# 01_PSU.net
KiCad netlist of a schematic drawn in Altium Designer
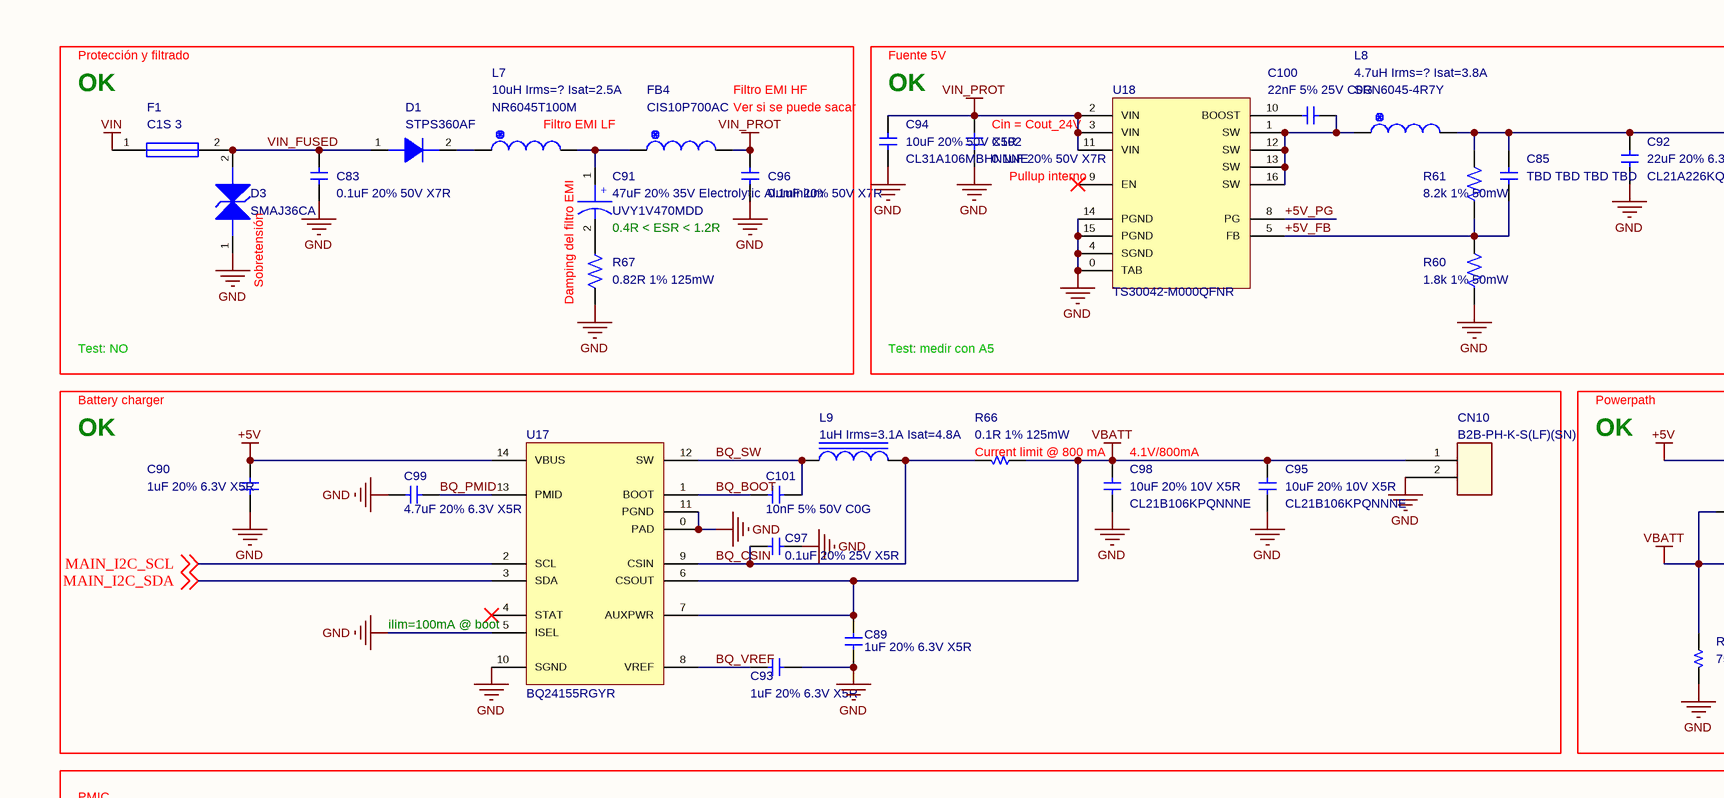
[diagram p0: 01_PSU.SchDoc, top left]
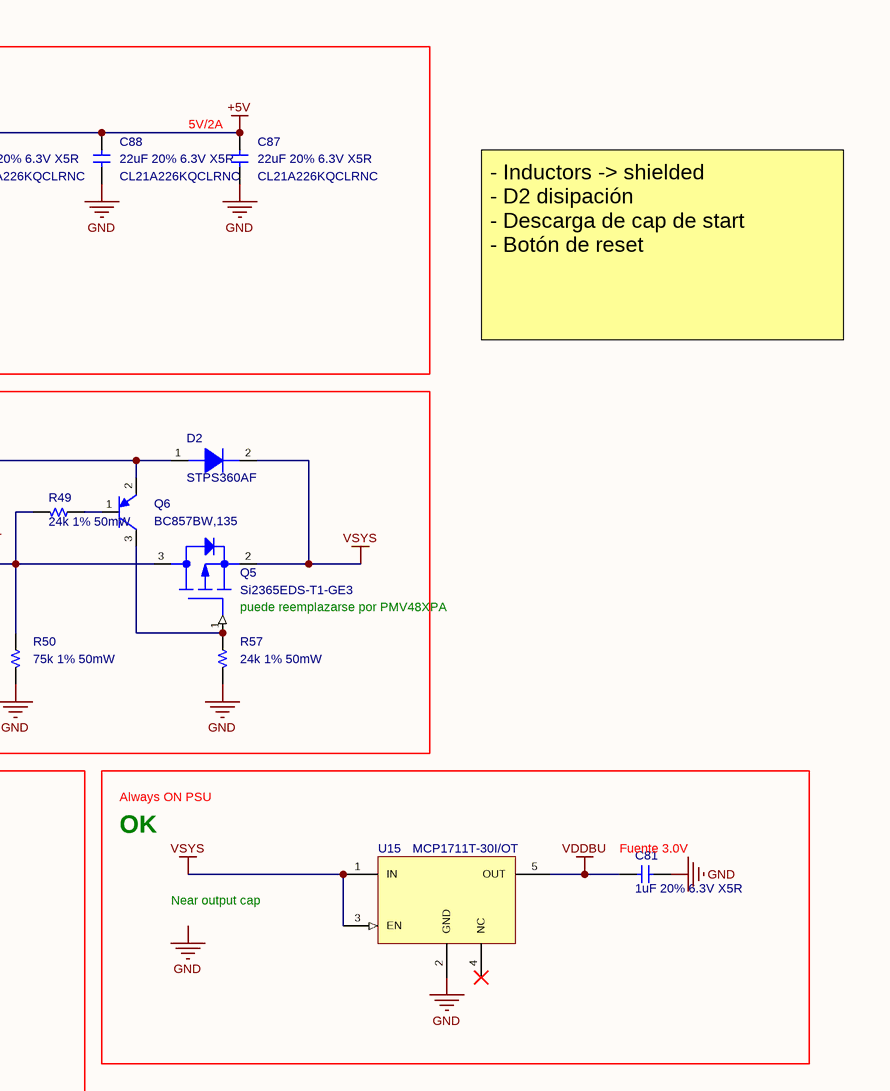
[diagram p1: 01_PSU.SchDoc, top right]
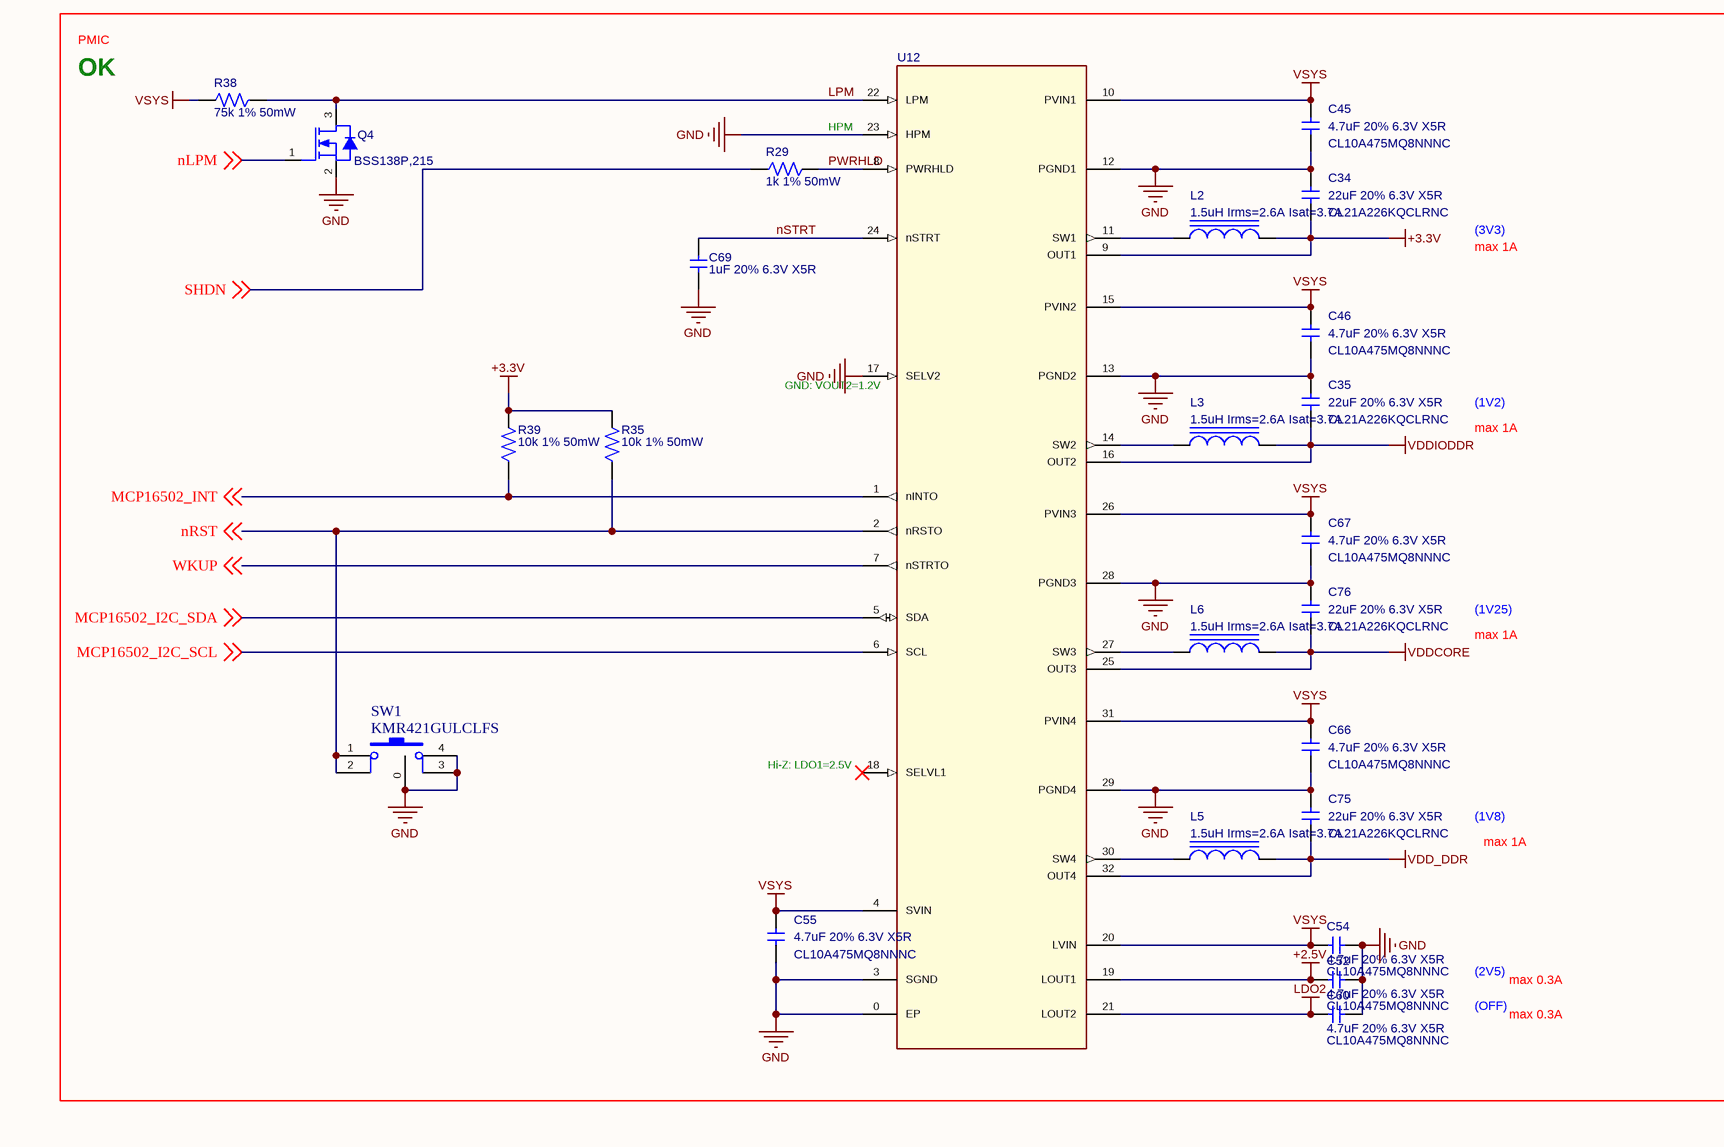
[diagram p2: 01_PSU.SchDoc, bottom left]

(export (version "E")
  (design (tool "Eeschema 10.0.6"))
  (components
    (comp (ref "C34")
      (value "22uF 20% 6.3V X5R")
      (footprint "CAPC2012X140N")
      (description "Capacitor, Ceramic")
      (fields
        (field (name "MFG") "SAMSUNG")
        (field (name "MFG_PN") "CL21A226KQCLRNC")
        (field (name "TOLERANCE") "20%")
        (field (name "FOOTPRINT CHECKED") "Assign OK, Footprint OK")
      )
      (libsource (lib "*") (part "C_Dup1"))
    )
    (comp (ref "C35")
      (value "22uF 20% 6.3V X5R")
      (footprint "CAPC2012X140N")
      (description "Capacitor, Ceramic")
      (fields
        (field (name "MFG") "SAMSUNG")
        (field (name "MFG_PN") "CL21A226KQCLRNC")
        (field (name "TOLERANCE") "20%")
        (field (name "FOOTPRINT CHECKED") "Assign OK, Footprint OK")
      )
      (libsource (lib "*") (part "C_Dup1"))
    )
    (comp (ref "C45")
      (value "4.7uF 20% 6.3V X5R")
      (footprint "CAPC1608X90N")
      (description "Capacitor, Ceramic")
      (fields
        (field (name "MFG") "SAMSUNG")
        (field (name "MFG_PN") "CL10A475MQ8NNNC")
        (field (name "TOLERANCE") "20%")
        (field (name "FOOTPRINT CHECKED") "Assign OK, Footprint OK")
      )
      (libsource (lib "*") (part "C_Dup1"))
    )
    (comp (ref "C46")
      (value "4.7uF 20% 6.3V X5R")
      (footprint "CAPC1608X90N")
      (description "Capacitor, Ceramic")
      (fields
        (field (name "MFG") "SAMSUNG")
        (field (name "MFG_PN") "CL10A475MQ8NNNC")
        (field (name "TOLERANCE") "20%")
        (field (name "FOOTPRINT CHECKED") "Assign OK, Footprint OK")
      )
      (libsource (lib "*") (part "C_Dup1"))
    )
    (comp (ref "C52")
      (value "4.7uF 20% 6.3V X5R")
      (footprint "CAPC1608X90N")
      (description "Capacitor, Ceramic")
      (fields
        (field (name "MFG") "SAMSUNG")
        (field (name "MFG_PN") "CL10A475MQ8NNNC")
        (field (name "TOLERANCE") "20%")
        (field (name "FOOTPRINT CHECKED") "Assign OK, Footprint OK")
      )
      (libsource (lib "*") (part "C_Dup1"))
    )
    (comp (ref "C54")
      (value "4.7uF 20% 6.3V X5R")
      (footprint "CAPC1608X90N")
      (description "Capacitor, Ceramic")
      (fields
        (field (name "MFG") "SAMSUNG")
        (field (name "MFG_PN") "CL10A475MQ8NNNC")
        (field (name "TOLERANCE") "20%")
        (field (name "FOOTPRINT CHECKED") "Assign OK, Footprint OK")
      )
      (libsource (lib "*") (part "C_Dup1"))
    )
    (comp (ref "C55")
      (value "4.7uF 20% 6.3V X5R")
      (footprint "CAPC1608X90N")
      (description "Capacitor, Ceramic")
      (fields
        (field (name "MFG") "SAMSUNG")
        (field (name "MFG_PN") "CL10A475MQ8NNNC")
        (field (name "TOLERANCE") "20%")
        (field (name "FOOTPRINT CHECKED") "Assign OK, Footprint OK")
      )
      (libsource (lib "*") (part "C_Dup1"))
    )
    (comp (ref "C60")
      (value "4.7uF 20% 6.3V X5R")
      (footprint "CAPC1608X90N")
      (description "Capacitor, Ceramic")
      (fields
        (field (name "MFG") "SAMSUNG")
        (field (name "MFG_PN") "CL10A475MQ8NNNC")
        (field (name "TOLERANCE") "20%")
        (field (name "FOOTPRINT CHECKED") "Assign OK, Footprint OK")
      )
      (libsource (lib "*") (part "C_Dup1"))
    )
    (comp (ref "C66")
      (value "4.7uF 20% 6.3V X5R")
      (footprint "CAPC1608X90N")
      (description "Capacitor, Ceramic")
      (fields
        (field (name "MFG") "SAMSUNG")
        (field (name "MFG_PN") "CL10A475MQ8NNNC")
        (field (name "TOLERANCE") "20%")
        (field (name "FOOTPRINT CHECKED") "Assign OK, Footprint OK")
      )
      (libsource (lib "*") (part "C_Dup1"))
    )
    (comp (ref "C67")
      (value "4.7uF 20% 6.3V X5R")
      (footprint "CAPC1608X90N")
      (description "Capacitor, Ceramic")
      (fields
        (field (name "MFG") "SAMSUNG")
        (field (name "MFG_PN") "CL10A475MQ8NNNC")
        (field (name "TOLERANCE") "20%")
        (field (name "FOOTPRINT CHECKED") "Assign OK, Footprint OK")
      )
      (libsource (lib "*") (part "C_Dup1"))
    )
    (comp (ref "C69")
      (value "1uF 20% 6.3V X5R")
      (footprint "CAPC1005N")
      (description "Capacitor, Ceramic")
      (fields
        (field (name "MFG") "SAMSUNG")
        (field (name "TOLERANCE") "20%")
        (field (name "FOOTPRINT CHECKED") "Assign OK, Footprint OK")
      )
      (libsource (lib "*") (part "C_Dup1"))
    )
    (comp (ref "C75")
      (value "22uF 20% 6.3V X5R")
      (footprint "CAPC2012X140N")
      (description "Capacitor, Ceramic")
      (fields
        (field (name "MFG") "SAMSUNG")
        (field (name "MFG_PN") "CL21A226KQCLRNC")
        (field (name "TOLERANCE") "20%")
        (field (name "FOOTPRINT CHECKED") "Assign OK, Footprint OK")
      )
      (libsource (lib "*") (part "C_Dup1"))
    )
    (comp (ref "C76")
      (value "22uF 20% 6.3V X5R")
      (footprint "CAPC2012X140N")
      (description "Capacitor, Ceramic")
      (fields
        (field (name "MFG") "SAMSUNG")
        (field (name "MFG_PN") "CL21A226KQCLRNC")
        (field (name "TOLERANCE") "20%")
        (field (name "FOOTPRINT CHECKED") "Assign OK, Footprint OK")
      )
      (libsource (lib "*") (part "C_Dup1"))
    )
    (comp (ref "C81")
      (value "1uF 20% 6.3V X5R")
      (footprint "CAPC1005N")
      (description "Capacitor, Ceramic")
      (fields
        (field (name "MFG") "SAMSUNG")
        (field (name "TOLERANCE") "20%")
        (field (name "FOOTPRINT CHECKED") "Assign OK, Footprint OK")
      )
      (libsource (lib "components") (part "C"))
    )
    (comp (ref "C83")
      (value "0.1uF 20% 50V X7R")
      (footprint "CAPC1608X90N")
      (description "Capacitor, Ceramic")
      (fields
        (field (name "MFG") "SAMSUNG")
        (field (name "TOLERANCE") "20%")
        (field (name "FOOTPRINT CHECKED") "Assign OK, Footprint OK")
      )
      (libsource (lib "*") (part "C_Dup1"))
    )
    (comp (ref "C85")
      (value "TBD TBD TBD TBD")
      (footprint "CAPC1005N")
      (description "Capacitor, Ceramic")
      (fields
        (field (name "MFG") "<GENERIC>")
        (field (name "TOLERANCE") "TBD")
        (field (name "FOOTPRINT CHECKED") "Assign OK, Footprint OK")
      )
      (libsource (lib "*") (part "C_Dup1"))
    )
    (comp (ref "C87")
      (value "22uF 20% 6.3V X5R")
      (footprint "CAPC2012X140N")
      (description "Capacitor, Ceramic")
      (fields
        (field (name "MFG") "SAMSUNG")
        (field (name "MFG_PN") "CL21A226KQCLRNC")
        (field (name "TOLERANCE") "20%")
        (field (name "FOOTPRINT CHECKED") "Assign OK, Footprint OK")
      )
      (libsource (lib "*") (part "C_Dup1"))
    )
    (comp (ref "C88")
      (value "22uF 20% 6.3V X5R")
      (footprint "CAPC2012X140N")
      (description "Capacitor, Ceramic")
      (fields
        (field (name "MFG") "SAMSUNG")
        (field (name "MFG_PN") "CL21A226KQCLRNC")
        (field (name "TOLERANCE") "20%")
        (field (name "FOOTPRINT CHECKED") "Assign OK, Footprint OK")
      )
      (libsource (lib "*") (part "C_Dup1"))
    )
    (comp (ref "C89")
      (value "1uF 20% 6.3V X5R")
      (footprint "CAPC1005N")
      (description "Capacitor, Ceramic")
      (fields
        (field (name "MFG") "SAMSUNG")
        (field (name "TOLERANCE") "20%")
        (field (name "FOOTPRINT CHECKED") "Assign OK, Footprint OK")
      )
      (libsource (lib "components") (part "C"))
    )
    (comp (ref "C90")
      (value "1uF 20% 6.3V X5R")
      (footprint "CAPC1005N")
      (description "Capacitor, Ceramic")
      (fields
        (field (name "MFG") "SAMSUNG")
        (field (name "TOLERANCE") "20%")
        (field (name "FOOTPRINT CHECKED") "Assign OK, Footprint OK")
      )
      (libsource (lib "*") (part "C_Dup1"))
    )
    (comp (ref "C91")
      (value "47uF 20% 35V Electrolytic Aluminium")
      (footprint "CAPPR2-5x12")
      (description "Capacitor, Electrolytic")
      (fields
        (field (name "MFG_PN") "UVY1V470MDD")
        (field (name "MFG") "NICHICON")
        (field (name "TOLERANCE") "20%")
        (field (name "FOOTPRINT CHECKED") "Assign OK, Footprint OK")
      )
      (libsource (lib "*") (part "CP"))
    )
    (comp (ref "C92")
      (value "22uF 20% 6.3V X5R")
      (footprint "CAPC2012X140N")
      (description "Capacitor, Ceramic")
      (fields
        (field (name "MFG") "SAMSUNG")
        (field (name "MFG_PN") "CL21A226KQCLRNC")
        (field (name "TOLERANCE") "20%")
        (field (name "FOOTPRINT CHECKED") "Assign OK, Footprint OK")
      )
      (libsource (lib "*") (part "C_Dup1"))
    )
    (comp (ref "C93")
      (value "1uF 20% 6.3V X5R")
      (footprint "CAPC1005N")
      (description "Capacitor, Ceramic")
      (fields
        (field (name "MFG") "SAMSUNG")
        (field (name "TOLERANCE") "20%")
        (field (name "FOOTPRINT CHECKED") "Assign OK, Footprint OK")
      )
      (libsource (lib "components") (part "C"))
    )
    (comp (ref "C94")
      (value "10uF 20% 50V X5R")
      (footprint "CAPC3216X180N")
      (description "Capacitor, Ceramic")
      (fields
        (field (name "MFG") "SAMSUNG")
        (field (name "MFG_PN") "CL31A106MBHNNNE")
        (field (name "TOLERANCE") "20%")
        (field (name "FOOTPRINT CHECKED") "Assign OK, Footprint OK")
      )
      (libsource (lib "*") (part "C_Dup1"))
    )
    (comp (ref "C95")
      (value "10uF 20% 10V X5R")
      (footprint "CAPC2012X140N")
      (description "Capacitor, Ceramic")
      (fields
        (field (name "MFG") "SAMSUNG")
        (field (name "MFG_PN") "CL21B106KPQNNNE")
        (field (name "TOLERANCE") "20%")
        (field (name "FOOTPRINT CHECKED") "Assign OK, Footprint OK")
      )
      (libsource (lib "*") (part "C_Dup1"))
    )
    (comp (ref "C96")
      (value "0.1uF 20% 50V X7R")
      (footprint "CAPC1608X90N")
      (description "Capacitor, Ceramic")
      (fields
        (field (name "MFG") "SAMSUNG")
        (field (name "TOLERANCE") "20%")
        (field (name "FOOTPRINT CHECKED") "Assign OK, Footprint OK")
      )
      (libsource (lib "*") (part "C_Dup1"))
    )
    (comp (ref "C97")
      (value "0.1uF 20% 25V X5R")
      (footprint "CAPC1005N")
      (description "Capacitor, Ceramic")
      (fields
        (field (name "MFG") "SAMSUNG")
        (field (name "TOLERANCE") "20%")
        (field (name "FOOTPRINT CHECKED") "Assign OK, Footprint OK")
      )
      (libsource (lib "*") (part "C_Dup1"))
    )
    (comp (ref "C98")
      (value "10uF 20% 10V X5R")
      (footprint "CAPC2012X140N")
      (description "Capacitor, Ceramic")
      (fields
        (field (name "MFG") "SAMSUNG")
        (field (name "MFG_PN") "CL21B106KPQNNNE")
        (field (name "TOLERANCE") "20%")
        (field (name "FOOTPRINT CHECKED") "Assign OK, Footprint OK")
      )
      (libsource (lib "*") (part "C_Dup1"))
    )
    (comp (ref "C99")
      (value "4.7uF 20% 6.3V X5R")
      (footprint "CAPC1608X90N")
      (description "Capacitor, Ceramic")
      (fields
        (field (name "MFG") "SAMSUNG")
        (field (name "TOLERANCE") "20%")
        (field (name "FOOTPRINT CHECKED") "Assign OK, Footprint OK")
      )
      (libsource (lib "components") (part "C"))
    )
    (comp (ref "C100")
      (value "22nF 5% 25V C0G")
      (footprint "CAPC1005N")
      (description "Capacitor, Ceramic")
      (fields
        (field (name "MFG") "<GENERIC>")
        (field (name "TOLERANCE") "5%")
        (field (name "FOOTPRINT CHECKED") "Assign OK, Footprint OK")
      )
      (libsource (lib "*") (part "C_Dup1"))
    )
    (comp (ref "C101")
      (value "10nF 5% 50V C0G")
      (footprint "CAPC1005N")
      (description "Capacitor, Ceramic")
      (fields
        (field (name "MFG") "<GENERIC>")
        (field (name "TOLERANCE") "5%")
        (field (name "FOOTPRINT CHECKED") "Assign OK, Footprint OK")
      )
      (libsource (lib "components") (part "C"))
    )
    (comp (ref "C102")
      (value "0.1uF 20% 50V X7R")
      (footprint "CAPC1608X90N")
      (description "Capacitor, Ceramic")
      (fields
        (field (name "MFG") "SAMSUNG")
        (field (name "TOLERANCE") "20%")
        (field (name "FOOTPRINT CHECKED") "Assign OK, Footprint OK")
      )
      (libsource (lib "*") (part "C_Dup1"))
    )
    (comp (ref "CN10")
      (value "B2B-PH-K-S(LF)(SN)")
      (footprint "B2B-PH-K-S(LF)(SN)")
      (description "Header, Male pins, 1x2, 2mm, Vertical")
      (fields (field (name "MFG") "JST") (field (name "FOOTPRINT CHECKED") "Assign OK, Footprint OK"))
      (libsource (lib "*") (part "CON2"))
    )
    (comp (ref "D1")
      (value "STPS360AF")
      (footprint "SODFL4725X105N")
      (description "DIODE")
      (fields (field (name "MFG") "ST") (field (name "FOOTPRINT CHECKED") "Assign OK, Footprint OK"))
      (libsource (lib "*") (part "DIODE_1"))
    )
    (comp (ref "D2")
      (value "STPS360AF")
      (footprint "SODFL4725X105N")
      (description "DIODE")
      (fields (field (name "MFG") "ST") (field (name "FOOTPRINT CHECKED") "Assign OK, Footprint OK"))
      (libsource (lib "*") (part "DIODE_1"))
    )
    (comp (ref "D3")
      (value "SMAJ36CA")
      (footprint "DIOM5226X203N")
      (description "TVS")
      (fields (field (name "MFG") "BOURNS") (field (name "FOOTPRINT CHECKED") "Assign OK, Footprint OK"))
      (libsource (lib "traz") (part "TVS"))
    )
    (comp (ref "F1")
      (value "C1S 3")
      (footprint "RESC3216N")
      (description "Fuse")
      (fields
        (field (name "MFG") "BEL")
        (field (name "POWER") "250mW")
        (field (name "FOOTPRINT CHECKED") "Assign OK, Footprint OK")
      )
      (libsource (lib "Miscellaneous Devices") (part "Fuse 1"))
    )
    (comp (ref "FB4")
      (value "CIS10P700AC")
      (footprint "INDC1608X95N")
      (description "Ferrite Bead")
      (fields (field (name "MFG") "SAMSUNG") (field (name "FOOTPRINT CHECKED") "Assign OK, Footprint OK"))
      (libsource (lib "*") (part "L"))
    )
    (comp (ref "L2")
      (value "1.5uH Irms=2.6A Isat=3.7A")
      (footprint "INDC2520N")
      (description "Inductor, Ferrite core")
      (fields (field (name "MFG") "TAIYO YUDEN") (field (name "FOOTPRINT CHECKED") "Assign OK, Footprint OK"))
      (libsource (lib "components") (part "L_CORE"))
    )
    (comp (ref "L3")
      (value "1.5uH Irms=2.6A Isat=3.7A")
      (footprint "INDC2520N")
      (description "Inductor, Ferrite core")
      (fields (field (name "MFG") "TAIYO YUDEN") (field (name "FOOTPRINT CHECKED") "Assign OK, Footprint OK"))
      (libsource (lib "components") (part "L_CORE"))
    )
    (comp (ref "L5")
      (value "1.5uH Irms=2.6A Isat=3.7A")
      (footprint "INDC2520N")
      (description "Inductor, Ferrite core")
      (fields (field (name "MFG") "TAIYO YUDEN") (field (name "FOOTPRINT CHECKED") "Assign OK, Footprint OK"))
      (libsource (lib "components") (part "L_CORE"))
    )
    (comp (ref "L6")
      (value "1.5uH Irms=2.6A Isat=3.7A")
      (footprint "INDC2520N")
      (description "Inductor, Ferrite core")
      (fields (field (name "MFG") "TAIYO YUDEN") (field (name "FOOTPRINT CHECKED") "Assign OK, Footprint OK"))
      (libsource (lib "components") (part "L_CORE"))
    )
    (comp (ref "L7")
      (value "10uH Irms=? Isat=2.5A")
      (footprint "NR6045")
      (description "Inductor, Ferrite core")
      (fields
        (field (name "MFG") "TAIYO YUDEN")
        (field (name "MFG_PN") "NR6045T100M")
        (field (name "FOOTPRINT CHECKED") "Assign OK, Footprint OK")
      )
      (libsource (lib "*") (part "L"))
    )
    (comp (ref "L8")
      (value "4.7uH Irms=? Isat=3.8A")
      (footprint "SRN6045")
      (description "Inductor, Ferrite core")
      (fields
        (field (name "MFG") "BOURNS")
        (field (name "MFG_PN") "SRN6045-4R7Y")
        (field (name "FOOTPRINT CHECKED") "Assign OK, Footprint OK")
      )
      (libsource (lib "*") (part "L"))
    )
    (comp (ref "L9")
      (value "1uH Irms=3.1A Isat=4.8A")
      (footprint "INDC2520N")
      (description "Inductor, Ferrite core")
      (fields (field (name "MFG") "TAIYO YUDEN") (field (name "FOOTPRINT CHECKED") "Assign OK, Footprint OK"))
      (libsource (lib "components") (part "L_CORE"))
    )
    (comp (ref "Q4")
      (value "BSS138P,215")
      (footprint "SOT95P230X110-3N")
      (description "MOSFET, N channel")
      (fields (field (name "MFG") "NXP") (field (name "FOOTPRINT CHECKED") "Assign OK, Footprint OK"))
      (libsource (lib "MCHP-CDB") (part "Transistor MOS-N GSD"))
    )
    (comp (ref "Q5")
      (value "Si2365EDS-T1-GE3")
      (footprint "SOT95P230X110-3N")
      (description "MOSFET, P channel")
      (fields (field (name "MFG") "VISHAY") (field (name "FOOTPRINT CHECKED") "Assign OK, Footprint OK"))
      (libsource (lib "traz") (part "DMG1013UW"))
    )
    (comp (ref "Q6")
      (value "BC857BW,135")
      (footprint "SOT65P210X110-3N")
      (description "PNP")
      (fields (field (name "MFG") "NXP") (field (name "FOOTPRINT CHECKED") "Assign OK, Footprint OK"))
      (libsource (lib "Motorola Discrete BJT") (part "MMBT2907LT1"))
    )
    (comp (ref "R29")
      (value "1k 1% 50mW")
      (footprint "RESC1005X40N")
      (description "Resistor, SMD")
      (fields
        (field (name "MFG") "<GENERIC>")
        (field (name "POWER") "50mW")
        (field (name "FOOTPRINT CHECKED") "Assign OK, Footprint OK")
      )
      (libsource (lib "*") (part "R"))
    )
    (comp (ref "R35")
      (value "10k 1% 50mW")
      (footprint "RESC1005X40N")
      (description "Resistor, SMD")
      (fields
        (field (name "MFG") "<GENERIC>")
        (field (name "POWER") "50mW")
        (field (name "FOOTPRINT CHECKED") "Assign OK, Footprint OK")
      )
      (libsource (lib "*") (part "R"))
    )
    (comp (ref "R38")
      (value "75k 1% 50mW")
      (footprint "RESC1005X40N")
      (description "Resistor, SMD")
      (fields
        (field (name "MFG") "<GENERIC>")
        (field (name "POWER") "50mW")
        (field (name "FOOTPRINT CHECKED") "Assign OK, Footprint OK")
      )
      (libsource (lib "*") (part "R"))
    )
    (comp (ref "R39")
      (value "10k 1% 50mW")
      (footprint "RESC1005X40N")
      (description "Resistor, SMD")
      (fields
        (field (name "MFG") "<GENERIC>")
        (field (name "POWER") "50mW")
        (field (name "FOOTPRINT CHECKED") "Assign OK, Footprint OK")
      )
      (libsource (lib "*") (part "R"))
    )
    (comp (ref "R49")
      (value "24k 1% 50mW")
      (footprint "RESC1005X40N")
      (description "Resistor, SMD")
      (fields
        (field (name "MFG") "<GENERIC>")
        (field (name "POWER") "50mW")
        (field (name "FOOTPRINT CHECKED") "Assign OK, Footprint OK")
      )
      (libsource (lib "components") (part "R"))
    )
    (comp (ref "R50")
      (value "75k 1% 50mW")
      (footprint "RESC1005X40N")
      (description "Resistor, SMD")
      (fields
        (field (name "MFG") "<GENERIC>")
        (field (name "POWER") "50mW")
        (field (name "FOOTPRINT CHECKED") "Assign OK, Footprint OK")
      )
      (libsource (lib "components") (part "R"))
    )
    (comp (ref "R57")
      (value "24k 1% 50mW")
      (footprint "RESC1005X40N")
      (description "Resistor, SMD")
      (fields
        (field (name "MFG") "<GENERIC>")
        (field (name "POWER") "50mW")
        (field (name "FOOTPRINT CHECKED") "Assign OK, Footprint OK")
      )
      (libsource (lib "components") (part "R"))
    )
    (comp (ref "R60")
      (value "1.8k 1% 50mW")
      (footprint "RESC1005X40N")
      (description "Resistor, SMD")
      (fields
        (field (name "MFG") "<GENERIC>")
        (field (name "POWER") "50mW")
        (field (name "FOOTPRINT CHECKED") "Assign OK, Footprint OK")
      )
      (libsource (lib "*") (part "R"))
    )
    (comp (ref "R61")
      (value "8.2k 1% 50mW")
      (footprint "RESC1005X40N")
      (description "Resistor, SMD")
      (fields
        (field (name "MFG") "<GENERIC>")
        (field (name "POWER") "50mW")
        (field (name "FOOTPRINT CHECKED") "Assign OK, Footprint OK")
      )
      (libsource (lib "*") (part "R"))
    )
    (comp (ref "R66")
      (value "0.1R 1% 125mW")
      (footprint "RESC2012X50N")
      (description "Resistor, SMD")
      (fields
        (field (name "MFG") "<GENERIC>")
        (field (name "POWER") "125mW")
        (field (name "FOOTPRINT CHECKED") "Assign OK, Footprint OK")
      )
      (libsource (lib "components") (part "R"))
    )
    (comp (ref "R67")
      (value "0.82R 1% 125mW")
      (footprint "RESC2012X50N")
      (description "Resistor, SMD")
      (fields
        (field (name "MFG") "<GENERIC>")
        (field (name "POWER") "125mW")
        (field (name "FOOTPRINT CHECKED") "Assign OK, Footprint OK")
      )
      (libsource (lib "*") (part "R"))
    )
    (comp (ref "SW1")
      (value "KMR421GULCLFS")
      (footprint "KMR4")
      (description "Switch")
      (fields (field (name "MFG") "C&K") (field (name "FOOTPRINT CHECKED") "Assign OK, Footprint OK"))
      (libsource (lib "sch") (part "SW-PB"))
    )
    (comp (ref "U12")
      (value "MCP16502TAC-E/S8B")
      (footprint "QFN50P500X500X90-33N")
      (description "High-Performance PMIC for SAMA5DX/SAM9X6 MPUs")
      (fields (field (name "MFG") "MICROCHIP") (field (name "FOOTPRINT CHECKED") "Assign OK, Footprint OK"))
      (libsource (lib "MCHP-CDB") (part "MCP16502 QFN-32"))
    )
    (comp (ref "U15")
      (value "MCP1711T-30I/OT")
      (footprint "SensorWireless:SOT95P284X122-5N")
      (description "Linear Voltage Regulator IC  1 Output  150mA SOT-25-5")
      (fields (field (name "MFG") "MICROCHIP") (field (name "FOOTPRINT CHECKED") "Assign OK, Footprint OK"))
      (libsource (lib "SensorWireless") (part "XC6504"))
    )
    (comp (ref "U17")
      (value "BQ24155RGYR")
      (footprint "VQFN14")
      (description "Charger IC Lithium Ion/Polymer 14-VQFN (3.5x3.5)")
      (fields (field (name "MFG") "TI") (field (name "FOOTPRINT CHECKED") "Assign OK, Footprint OK"))
      (libsource (lib "sch") (part "BQ24155RGYR"))
    )
    (comp (ref "U18")
      (value "TS30042-M000QFNR")
      (footprint "QFN50P300X300X100-17AN")
      (description "24V Input, 1A/2A Output, High Efficiency Synchronous Buck Regulator with Power Good Indication")
      (fields (field (name "MFG") "SEMTECH") (field (name "FOOTPRINT CHECKED") "Assign OK, Footprint OK"))
      (libsource (lib "sch") (part "MCP16322"))
    )
  )
  (nets
    (net (code "1") (name "+2.5V") (class "Default")
      (node (ref "C52") (pin "1") (pinfunction "1_1") (pintype "passive"))
      (node (ref "U12") (pin "19") (pinfunction "LOUT1_19") (pintype "power_in"))
    )
    (net (code "2") (name "+3.3V") (class "Default")
      (node (ref "C34") (pin "2") (pinfunction "2_2") (pintype "passive"))
      (node (ref "L2") (pin "2") (pinfunction "2_2") (pintype "passive"))
      (node (ref "R35") (pin "2") (pinfunction "2_2") (pintype "passive"))
      (node (ref "R39") (pin "2") (pinfunction "2_2") (pintype "passive"))
      (node (ref "U12") (pin "9") (pinfunction "OUT1_9") (pintype "power_in"))
    )
    (net (code "3") (name "+5V") (class "Default")
      (node (ref "C85") (pin "2") (pinfunction "2_2") (pintype "passive"))
      (node (ref "C87") (pin "1") (pinfunction "1_1") (pintype "passive"))
      (node (ref "C88") (pin "1") (pinfunction "1_1") (pintype "passive"))
      (node (ref "C90") (pin "1") (pinfunction "1_1") (pintype "passive"))
      (node (ref "C92") (pin "1") (pinfunction "1_1") (pintype "passive"))
      (node (ref "D2") (pin "1") (pinfunction "A_1") (pintype "passive"))
      (node (ref "L8") (pin "2") (pinfunction "2_2") (pintype "passive"))
      (node (ref "Q6") (pin "2") (pinfunction "E_2") (pintype "passive"))
      (node (ref "R61") (pin "2") (pinfunction "2_2") (pintype "passive"))
      (node (ref "U17") (pin "14") (pinfunction "VBUS_14") (pintype "passive"))
    )
    (net (code "4") (name "/+5V_FB") (class "Default")
      (node (ref "C85") (pin "1") (pinfunction "1_1") (pintype "passive"))
      (node (ref "R60") (pin "2") (pinfunction "2_2") (pintype "passive"))
      (node (ref "R61") (pin "1") (pinfunction "1_1") (pintype "passive"))
      (node (ref "U18") (pin "5") (pinfunction "FB_5") (pintype "passive"))
    )
    (net (code "5") (name "/+5V_PG") (class "Default")
      (node (ref "U18") (pin "8") (pinfunction "PG_8") (pintype "passive"))
    )
    (net (code "6") (name "/BQ_BOOT") (class "Default")
      (node (ref "C101") (pin "2") (pinfunction "2_2") (pintype "passive"))
      (node (ref "U17") (pin "1") (pinfunction "BOOT_1") (pintype "passive"))
    )
    (net (code "7") (name "/BQ_CSIN") (class "Default")
      (node (ref "C97") (pin "2") (pinfunction "2_2") (pintype "passive"))
      (node (ref "L9") (pin "2") (pinfunction "2_2") (pintype "passive"))
      (node (ref "R66") (pin "2") (pinfunction "2_2") (pintype "passive"))
      (node (ref "U17") (pin "9") (pinfunction "CSIN_9") (pintype "passive"))
    )
    (net (code "8") (name "/BQ_PMID") (class "Default")
      (node (ref "C99") (pin "1") (pinfunction "1_1") (pintype "passive"))
      (node (ref "U17") (pin "13") (pinfunction "PMID_13") (pintype "passive"))
    )
    (net (code "9") (name "/BQ_SW") (class "Default")
      (node (ref "C101") (pin "1") (pinfunction "1_1") (pintype "passive"))
      (node (ref "L9") (pin "1") (pinfunction "1_1") (pintype "passive"))
      (node (ref "U17") (pin "12") (pinfunction "SW_12") (pintype "passive"))
    )
    (net (code "10") (name "/BQ_VREF") (class "Default")
      (node (ref "C93") (pin "2") (pinfunction "2_2") (pintype "passive"))
      (node (ref "U17") (pin "8") (pinfunction "VREF_8") (pintype "passive"))
    )
    (net (code "11") (name "/LPM") (class "Default")
      (node (ref "Q4") (pin "3") (pinfunction "D_3") (pintype "passive"))
      (node (ref "R38") (pin "1") (pinfunction "1_1") (pintype "passive"))
      (node (ref "U12") (pin "22") (pinfunction "LPM_22") (pintype "input"))
    )
    (net (code "12") (name "/PWRHLD") (class "Default")
      (node (ref "R29") (pin "2") (pinfunction "2_2") (pintype "passive"))
      (node (ref "U12") (pin "8") (pinfunction "PWRHLD_8") (pintype "input"))
    )
    (net (code "13") (name "/VIN_FUSED") (class "Default")
      (node (ref "C83") (pin "1") (pinfunction "1_1") (pintype "passive"))
      (node (ref "D1") (pin "1") (pinfunction "A_1") (pintype "passive"))
      (node (ref "D3") (pin "2") (pinfunction "CATHODE_2") (pintype "passive"))
      (node (ref "F1") (pin "2") (pinfunction "2_2") (pintype "passive"))
    )
    (net (code "14") (name "/nSTRT") (class "Default")
      (node (ref "C69") (pin "1") (pinfunction "1_1") (pintype "passive"))
      (node (ref "U12") (pin "24") (pinfunction "nSTRT_24") (pintype "input"))
    )
    (net (code "15") (name "GND") (class "Default")
      (node (ref "C102") (pin "2") (pinfunction "2_2") (pintype "passive"))
      (node (ref "C34") (pin "1") (pinfunction "1_1") (pintype "passive"))
      (node (ref "C35") (pin "1") (pinfunction "1_1") (pintype "passive"))
      (node (ref "C45") (pin "2") (pinfunction "2_2") (pintype "passive"))
      (node (ref "C46") (pin "2") (pinfunction "2_2") (pintype "passive"))
      (node (ref "C52") (pin "2") (pinfunction "2_2") (pintype "passive"))
      (node (ref "C54") (pin "2") (pinfunction "2_2") (pintype "passive"))
      (node (ref "C55") (pin "2") (pinfunction "2_2") (pintype "passive"))
      (node (ref "C60") (pin "2") (pinfunction "2_2") (pintype "passive"))
      (node (ref "C66") (pin "2") (pinfunction "2_2") (pintype "passive"))
      (node (ref "C67") (pin "2") (pinfunction "2_2") (pintype "passive"))
      (node (ref "C69") (pin "2") (pinfunction "2_2") (pintype "passive"))
      (node (ref "C75") (pin "1") (pinfunction "1_1") (pintype "passive"))
      (node (ref "C76") (pin "1") (pinfunction "1_1") (pintype "passive"))
      (node (ref "C81") (pin "1") (pinfunction "1_1") (pintype "passive"))
      (node (ref "C83") (pin "2") (pinfunction "2_2") (pintype "passive"))
      (node (ref "C87") (pin "2") (pinfunction "2_2") (pintype "passive"))
      (node (ref "C88") (pin "2") (pinfunction "2_2") (pintype "passive"))
      (node (ref "C89") (pin "1") (pinfunction "1_1") (pintype "passive"))
      (node (ref "C90") (pin "2") (pinfunction "2_2") (pintype "passive"))
      (node (ref "C92") (pin "2") (pinfunction "2_2") (pintype "passive"))
      (node (ref "C93") (pin "1") (pinfunction "1_1") (pintype "passive"))
      (node (ref "C94") (pin "2") (pinfunction "2_2") (pintype "passive"))
      (node (ref "C95") (pin "2") (pinfunction "2_2") (pintype "passive"))
      (node (ref "C96") (pin "2") (pinfunction "2_2") (pintype "passive"))
      (node (ref "C97") (pin "1") (pinfunction "1_1") (pintype "passive"))
      (node (ref "C98") (pin "2") (pinfunction "2_2") (pintype "passive"))
      (node (ref "C99") (pin "2") (pinfunction "2_2") (pintype "passive"))
      (node (ref "CN10") (pin "2") (pinfunction "2_2") (pintype "passive"))
      (node (ref "D3") (pin "1") (pinfunction "ANODE_1") (pintype "passive"))
      (node (ref "Q4") (pin "2") (pinfunction "S_2") (pintype "passive"))
      (node (ref "R50") (pin "2") (pinfunction "2_2") (pintype "passive"))
      (node (ref "R57") (pin "2") (pinfunction "2_2") (pintype "passive"))
      (node (ref "R60") (pin "1") (pinfunction "1_1") (pintype "passive"))
      (node (ref "R67") (pin "2") (pinfunction "2_2") (pintype "passive"))
      (node (ref "SW1") (pin "0") (pinfunction "M_0") (pintype "passive"))
      (node (ref "SW1") (pin "3") (pinfunction "3_3") (pintype "passive"))
      (node (ref "SW1") (pin "4") (pinfunction "4_4") (pintype "passive"))
      (node (ref "U12") (pin "0") (pinfunction "EP_0") (pintype "power_in"))
      (node (ref "U12") (pin "12") (pinfunction "PGND1_12") (pintype "power_in"))
      (node (ref "U12") (pin "13") (pinfunction "PGND2_13") (pintype "power_in"))
      (node (ref "U12") (pin "17") (pinfunction "SELV2_17") (pintype "input"))
      (node (ref "U12") (pin "23") (pinfunction "HPM_23") (pintype "input"))
      (node (ref "U12") (pin "28") (pinfunction "PGND3_28") (pintype "power_in"))
      (node (ref "U12") (pin "29") (pinfunction "PGND4_29") (pintype "power_in"))
      (node (ref "U12") (pin "3") (pinfunction "SGND_3") (pintype "power_in"))
      (node (ref "U15") (pin "2") (pinfunction "GND_2") (pintype "power_in"))
      (node (ref "U17") (pin "0") (pinfunction "PAD_0") (pintype "passive"))
      (node (ref "U17") (pin "10") (pinfunction "SGND_10") (pintype "passive"))
      (node (ref "U17") (pin "11") (pinfunction "PGND_11") (pintype "passive"))
      (node (ref "U17") (pin "5") (pinfunction "ISEL_5") (pintype "passive"))
      (node (ref "U18") (pin "0") (pinfunction "TAB_0") (pintype "passive"))
      (node (ref "U18") (pin "14") (pinfunction "PGND_14") (pintype "passive"))
      (node (ref "U18") (pin "15") (pinfunction "PGND_15") (pintype "passive"))
      (node (ref "U18") (pin "4") (pinfunction "SGND_4") (pintype "passive"))
    )
    (net (code "16") (name "LDO2") (class "Default")
      (node (ref "C60") (pin "1") (pinfunction "1_1") (pintype "passive"))
      (node (ref "U12") (pin "21") (pinfunction "LOUT2_21") (pintype "power_in"))
    )
    (net (code "17") (name "MAIN_I2C_SCL") (class "Default")
      (node (ref "U17") (pin "2") (pinfunction "SCL_2") (pintype "passive"))
    )
    (net (code "18") (name "MAIN_I2C_SDA") (class "Default")
      (node (ref "U17") (pin "3") (pinfunction "SDA_3") (pintype "passive"))
    )
    (net (code "19") (name "MCP16502_I2C_SCL") (class "Default")
      (node (ref "U12") (pin "6") (pinfunction "SCL_6") (pintype "input"))
    )
    (net (code "20") (name "MCP16502_I2C_SDA") (class "Default")
      (node (ref "U12") (pin "5") (pinfunction "SDA_5") (pintype "bidirectional"))
    )
    (net (code "21") (name "MCP16502_INT") (class "Default")
      (node (ref "R39") (pin "1") (pinfunction "1_1") (pintype "passive"))
      (node (ref "U12") (pin "1") (pinfunction "nINTO_1") (pintype "output"))
    )
    (net (code "22") (name "Net-(C91-Pad1)") (class "Default")
      (node (ref "C91") (pin "1") (pinfunction "1_1") (pintype "passive"))
      (node (ref "FB4") (pin "1") (pinfunction "1_1") (pintype "passive"))
      (node (ref "L7") (pin "2") (pinfunction "2_2") (pintype "passive"))
    )
    (net (code "23") (name "Net-(C91-Pad2)") (class "Default")
      (node (ref "C91") (pin "2") (pinfunction "2_2") (pintype "passive"))
      (node (ref "R67") (pin "1") (pinfunction "1_1") (pintype "passive"))
    )
    (net (code "24") (name "Net-(C100-Pad1)") (class "Default")
      (node (ref "C100") (pin "1") (pinfunction "1_1") (pintype "passive"))
      (node (ref "L8") (pin "1") (pinfunction "1_1") (pintype "passive"))
      (node (ref "U18") (pin "1") (pinfunction "SW_1") (pintype "passive"))
      (node (ref "U18") (pin "12") (pinfunction "SW_12") (pintype "passive"))
      (node (ref "U18") (pin "13") (pinfunction "SW_13") (pintype "passive"))
      (node (ref "U18") (pin "16") (pinfunction "SW_16") (pintype "passive"))
    )
    (net (code "25") (name "Net-(D1-K)") (class "Default")
      (node (ref "D1") (pin "2") (pinfunction "K_2") (pintype "passive"))
      (node (ref "L7") (pin "1") (pinfunction "1_1") (pintype "passive"))
    )
    (net (code "26") (name "Net-(Q5-GATE)") (class "Default")
      (node (ref "Q5") (pin "1") (pinfunction "GATE_1") (pintype "input"))
      (node (ref "Q6") (pin "3") (pinfunction "C_3") (pintype "passive"))
      (node (ref "R57") (pin "1") (pinfunction "1_1") (pintype "passive"))
    )
    (net (code "27") (name "Net-(Q6-B)") (class "Default")
      (node (ref "Q6") (pin "1") (pinfunction "B_1") (pintype "passive"))
      (node (ref "R49") (pin "1") (pinfunction "1_1") (pintype "passive"))
    )
    (net (code "28") (name "Net-(U12-SW1)") (class "Default")
      (node (ref "L2") (pin "1") (pinfunction "1_1") (pintype "passive"))
      (node (ref "U12") (pin "11") (pinfunction "SW1_11") (pintype "output"))
    )
    (net (code "29") (name "Net-(U12-SW2)") (class "Default")
      (node (ref "L3") (pin "1") (pinfunction "1_1") (pintype "passive"))
      (node (ref "U12") (pin "14") (pinfunction "SW2_14") (pintype "output"))
    )
    (net (code "30") (name "Net-(U12-SW3)") (class "Default")
      (node (ref "L6") (pin "1") (pinfunction "1_1") (pintype "passive"))
      (node (ref "U12") (pin "27") (pinfunction "SW3_27") (pintype "output"))
    )
    (net (code "31") (name "Net-(U12-SW4)") (class "Default")
      (node (ref "L5") (pin "1") (pinfunction "1_1") (pintype "passive"))
      (node (ref "U12") (pin "30") (pinfunction "SW4_30") (pintype "output"))
    )
    (net (code "32") (name "Net-(U18-BOOST)") (class "Default")
      (node (ref "C100") (pin "2") (pinfunction "2_2") (pintype "passive"))
      (node (ref "U18") (pin "10") (pinfunction "BOOST_10") (pintype "passive"))
    )
    (net (code "33") (name "SHDN") (class "Default")
      (node (ref "R29") (pin "1") (pinfunction "1_1") (pintype "passive"))
    )
    (net (code "34") (name "VBATT") (class "Default")
      (node (ref "C89") (pin "2") (pinfunction "2_2") (pintype "passive"))
      (node (ref "C95") (pin "1") (pinfunction "1_1") (pintype "passive"))
      (node (ref "C98") (pin "1") (pinfunction "1_1") (pintype "passive"))
      (node (ref "CN10") (pin "1") (pinfunction "1_1") (pintype "passive"))
      (node (ref "Q5") (pin "3") (pinfunction "DRAIN_3") (pintype "passive"))
      (node (ref "R49") (pin "2") (pinfunction "2_2") (pintype "passive"))
      (node (ref "R50") (pin "1") (pinfunction "1_1") (pintype "passive"))
      (node (ref "R66") (pin "1") (pinfunction "1_1") (pintype "passive"))
      (node (ref "U17") (pin "6") (pinfunction "CSOUT_6") (pintype "passive"))
      (node (ref "U17") (pin "7") (pinfunction "AUXPWR_7") (pintype "passive"))
    )
    (net (code "35") (name "VDDBU") (class "Default")
      (node (ref "C81") (pin "2") (pinfunction "2_2") (pintype "passive"))
      (node (ref "U15") (pin "5") (pinfunction "OUT_5") (pintype "power_in"))
    )
    (net (code "36") (name "VDDCORE") (class "Default")
      (node (ref "C76") (pin "2") (pinfunction "2_2") (pintype "passive"))
      (node (ref "L6") (pin "2") (pinfunction "2_2") (pintype "passive"))
      (node (ref "U12") (pin "25") (pinfunction "OUT3_25") (pintype "power_in"))
    )
    (net (code "37") (name "VDDIODDR") (class "Default")
      (node (ref "C35") (pin "2") (pinfunction "2_2") (pintype "passive"))
      (node (ref "L3") (pin "2") (pinfunction "2_2") (pintype "passive"))
      (node (ref "U12") (pin "16") (pinfunction "OUT2_16") (pintype "power_in"))
    )
    (net (code "38") (name "VDD_DDR") (class "Default")
      (node (ref "C75") (pin "2") (pinfunction "2_2") (pintype "passive"))
      (node (ref "L5") (pin "2") (pinfunction "2_2") (pintype "passive"))
      (node (ref "U12") (pin "32") (pinfunction "OUT4_32") (pintype "power_in"))
    )
    (net (code "39") (name "VIN") (class "Default")
      (node (ref "F1") (pin "1") (pinfunction "1_1") (pintype "passive"))
    )
    (net (code "40") (name "VIN_PROT") (class "Default")
      (node (ref "C102") (pin "1") (pinfunction "1_1") (pintype "passive"))
      (node (ref "C94") (pin "1") (pinfunction "1_1") (pintype "passive"))
      (node (ref "C96") (pin "1") (pinfunction "1_1") (pintype "passive"))
      (node (ref "FB4") (pin "2") (pinfunction "2_2") (pintype "passive"))
      (node (ref "U18") (pin "11") (pinfunction "VIN_11") (pintype "passive"))
      (node (ref "U18") (pin "2") (pinfunction "VIN_2") (pintype "passive"))
      (node (ref "U18") (pin "3") (pinfunction "VIN_3") (pintype "passive"))
    )
    (net (code "41") (name "VSYS") (class "Default")
      (node (ref "C45") (pin "1") (pinfunction "1_1") (pintype "passive"))
      (node (ref "C46") (pin "1") (pinfunction "1_1") (pintype "passive"))
      (node (ref "C54") (pin "1") (pinfunction "1_1") (pintype "passive"))
      (node (ref "C55") (pin "1") (pinfunction "1_1") (pintype "passive"))
      (node (ref "C66") (pin "1") (pinfunction "1_1") (pintype "passive"))
      (node (ref "C67") (pin "1") (pinfunction "1_1") (pintype "passive"))
      (node (ref "D2") (pin "2") (pinfunction "K_2") (pintype "passive"))
      (node (ref "Q5") (pin "2") (pinfunction "SOURCE_2") (pintype "passive"))
      (node (ref "R38") (pin "2") (pinfunction "2_2") (pintype "passive"))
      (node (ref "U12") (pin "10") (pinfunction "PVIN1_10") (pintype "power_in"))
      (node (ref "U12") (pin "15") (pinfunction "PVIN2_15") (pintype "power_in"))
      (node (ref "U12") (pin "20") (pinfunction "LVIN_20") (pintype "power_in"))
      (node (ref "U12") (pin "26") (pinfunction "PVIN3_26") (pintype "power_in"))
      (node (ref "U12") (pin "31") (pinfunction "PVIN4_31") (pintype "power_in"))
      (node (ref "U12") (pin "4") (pinfunction "SVIN_4") (pintype "power_in"))
      (node (ref "U15") (pin "1") (pinfunction "IN_1") (pintype "power_in"))
      (node (ref "U15") (pin "3") (pinfunction "EN_3") (pintype "input"))
    )
    (net (code "42") (name "WKUP") (class "Default")
      (node (ref "U12") (pin "7") (pinfunction "nSTRTO_7") (pintype "output"))
    )
    (net (code "43") (name "nLPM") (class "Default")
      (node (ref "Q4") (pin "1") (pinfunction "G_1") (pintype "passive"))
    )
    (net (code "44") (name "nRST") (class "Default")
      (node (ref "R35") (pin "1") (pinfunction "1_1") (pintype "passive"))
      (node (ref "SW1") (pin "1") (pinfunction "1_1") (pintype "passive"))
      (node (ref "SW1") (pin "2") (pinfunction "2_2") (pintype "passive"))
      (node (ref "U12") (pin "2") (pinfunction "nRSTO_2") (pintype "output"))
    )
    (net (code "45") (name "unconnected-(U12-SELVL1-Pad18)") (class "Default")
      (node (ref "U12") (pin "18") (pinfunction "SELVL1_18") (pintype "input+no_connect"))
    )
    (net (code "46") (name "unconnected-(U15-NC-Pad4)") (class "Default")
      (node (ref "U15") (pin "4") (pinfunction "NC_4") (pintype "tri_state+no_connect"))
    )
    (net (code "47") (name "unconnected-(U17-STAT-Pad4)") (class "Default")
      (node (ref "U17") (pin "4") (pinfunction "STAT_4") (pintype "passive+no_connect"))
    )
    (net (code "48") (name "unconnected-(U18-EN-Pad9)") (class "Default")
      (node (ref "U18") (pin "9") (pinfunction "EN_9") (pintype "passive+no_connect"))
    )
  )
)
